# Parking_Lot_System_Main_Board.net
KiCad netlist of a schematic drawn in EAGLE
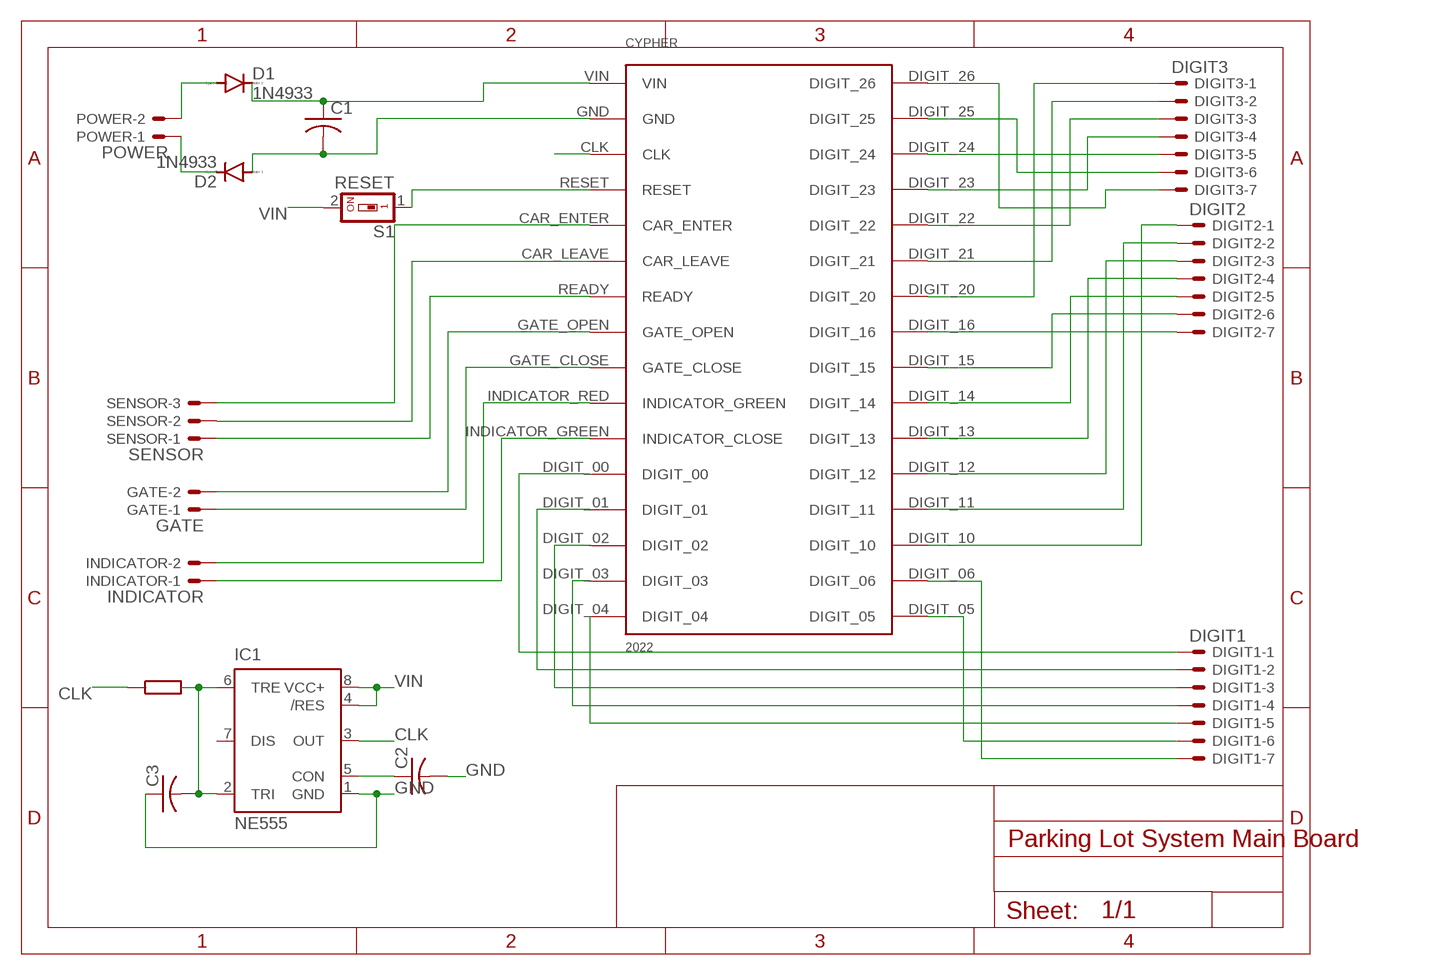
[diagram p0: schematic, sheet 1]

(export (version "E")
  (design (tool "Eeschema 10.0.6"))
  (components
    (comp (ref "C1")
      (value "C-US050-030X075")
      (footprint "eagle-import:C050-030X075")
      (libsource (lib "eagle-import") (part "C-US050-030X075"))
    )
    (comp (ref "C2")
      (value "C-US050-030X075")
      (footprint "eagle-import:C050-030X075")
      (libsource (lib "eagle-import") (part "C-US050-030X075"))
    )
    (comp (ref "C3")
      (value "C-US050-030X075")
      (footprint "eagle-import:C050-030X075")
      (libsource (lib "eagle-import") (part "C-US050-030X075"))
    )
    (comp (ref "CYPHER")
      (value "CYPHER2022")
      (footprint "eagle-import:CYPHER")
      (libsource (lib "eagle-import") (part "CYPHER2022"))
    )
    (comp (ref "D1")
      (value "1N4933")
      (footprint "eagle-import:DO41-10")
      (libsource (lib "eagle-import") (part "1N4933"))
    )
    (comp (ref "D2")
      (value "1N4933")
      (footprint "eagle-import:DO41-10")
      (libsource (lib "eagle-import") (part "1N4933"))
    )
    (comp (ref "DIGIT1")
      (value "DIGIT1")
      (footprint "eagle-import:22-23-2071")
      (fields (field (name "MF") "MOLEX") (field (name "MPN") "22-23-2071"))
      (libsource (lib "eagle-import") (part "22-23-2071"))
    )
    (comp (ref "DIGIT2")
      (value "DIGIT2")
      (footprint "eagle-import:22-23-2071")
      (fields (field (name "MF") "MOLEX") (field (name "MPN") "22-23-2071"))
      (libsource (lib "eagle-import") (part "22-23-2071"))
    )
    (comp (ref "DIGIT3")
      (value "DIGIT3")
      (footprint "eagle-import:22-23-2071")
      (fields (field (name "MF") "MOLEX") (field (name "MPN") "22-23-2071"))
      (libsource (lib "eagle-import") (part "22-23-2071"))
    )
    (comp (ref "GATE")
      (value "GATE")
      (footprint "eagle-import:22-23-2021")
      (fields (field (name "MF") "MOLEX") (field (name "MPN") "22-23-2021"))
      (libsource (lib "eagle-import") (part "22-23-2021"))
    )
    (comp (ref "IC1")
      (value "NE555")
      (footprint "eagle-import:DIL-08")
      (fields (field (name "MF") "Arrow Electronics") (field (name "MPN") "NE555N"))
      (libsource (lib "eagle-import") (part "NE555"))
    )
    (comp (ref "INDICATOR")
      (value "INDICATOR")
      (footprint "eagle-import:22-23-2021")
      (fields (field (name "MF") "MOLEX") (field (name "MPN") "22-23-2021"))
      (libsource (lib "eagle-import") (part "22-23-2021"))
    )
    (comp (ref "POWER")
      (value "POWER")
      (footprint "eagle-import:22-23-2021")
      (fields (field (name "MF") "MOLEX") (field (name "MPN") "22-23-2021"))
      (libsource (lib "eagle-import") (part "22-23-2021"))
    )
    (comp (ref "S1")
      (value "RESET")
      (footprint "eagle-import:SMS-001")
      (libsource (lib "eagle-import") (part "SWS001"))
    )
    (comp (ref "SENSOR")
      (value "SENSOR")
      (footprint "eagle-import:22-23-2031")
      (fields (field (name "MF") "MOLEX") (field (name "MPN") "22-23-2031"))
      (libsource (lib "eagle-import") (part "22-23-2031"))
    )
  )
  (nets
    (net (code "1") (name "/CLK") (class "Default")
      (node (ref "CYPHER") (pin "CLK") (pinfunction "CLK_CLK") (pintype "bidirectional"))
      (node (ref "IC1") (pin "3") (pinfunction "OUT_3") (pintype "output"))
    )
    (net (code "2") (name "/GND") (class "Default")
      (node (ref "C1") (pin "2") (pinfunction "2_2") (pintype "passive"))
      (node (ref "C2") (pin "2") (pinfunction "2_2") (pintype "passive"))
      (node (ref "C3") (pin "1") (pinfunction "1_1") (pintype "passive"))
      (node (ref "CYPHER") (pin "GND") (pinfunction "GND_GND") (pintype "bidirectional"))
      (node (ref "D2") (pin "A") (pinfunction "A_A") (pintype "passive"))
      (node (ref "IC1") (pin "1") (pinfunction "GND_1") (pintype "power_in"))
    )
    (net (code "3") (name "/VIN") (class "Default")
      (node (ref "C1") (pin "1") (pinfunction "1_1") (pintype "passive"))
      (node (ref "CYPHER") (pin "VIN") (pinfunction "VIN_VIN") (pintype "bidirectional"))
      (node (ref "D1") (pin "C") (pinfunction "C_C") (pintype "passive"))
      (node (ref "IC1") (pin "4") (pinfunction "/RES_4") (pintype "input"))
      (node (ref "IC1") (pin "8") (pinfunction "VCC+_8") (pintype "power_in"))
      (node (ref "S1") (pin "2") (pinfunction "2_2") (pintype "passive"))
    )
    (net (code "4") (name "Net-(CYPHER-INDICATOR_CLOSE)") (class "Default")
      (node (ref "CYPHER") (pin "INDICATOR_GREEN") (pinfunction "INDICATOR_CLOSE_INDICATOR_GREEN") (pintype "bidirectional"))
      (node (ref "INDICATOR") (pin "1") (pinfunction "S_1") (pintype "passive"))
    )
    (net (code "5") (name "Net-(CYPHER-INDICATOR_GREEN)") (class "Default")
      (node (ref "CYPHER") (pin "INDICATOR_RED") (pinfunction "INDICATOR_GREEN_INDICATOR_RED") (pintype "bidirectional"))
      (node (ref "INDICATOR") (pin "2") (pinfunction "S_2") (pintype "passive"))
    )
    (net (code "6") (name "Net-(CYPHER-PadRESET)") (class "Default")
      (node (ref "CYPHER") (pin "RESET") (pinfunction "RESET_RESET") (pintype "bidirectional"))
      (node (ref "S1") (pin "1") (pinfunction "1_1") (pintype "passive"))
    )
    (net (code "7") (name "Net-(DIGIT1A-S)") (class "Default")
      (node (ref "CYPHER") (pin "DIGIT_00") (pinfunction "DIGIT_00_DIGIT_00") (pintype "bidirectional"))
      (node (ref "DIGIT1") (pin "1") (pinfunction "S_1") (pintype "passive"))
    )
    (net (code "8") (name "Net-(DIGIT1B-S)") (class "Default")
      (node (ref "CYPHER") (pin "DIGIT_01") (pinfunction "DIGIT_01_DIGIT_01") (pintype "bidirectional"))
      (node (ref "DIGIT1") (pin "2") (pinfunction "S_2") (pintype "passive"))
    )
    (net (code "9") (name "Net-(DIGIT1C-S)") (class "Default")
      (node (ref "CYPHER") (pin "DIGIT_02") (pinfunction "DIGIT_02_DIGIT_02") (pintype "bidirectional"))
      (node (ref "DIGIT1") (pin "3") (pinfunction "S_3") (pintype "passive"))
    )
    (net (code "10") (name "Net-(DIGIT1D-S)") (class "Default")
      (node (ref "CYPHER") (pin "DIGIT_03") (pinfunction "DIGIT_03_DIGIT_03") (pintype "bidirectional"))
      (node (ref "DIGIT1") (pin "4") (pinfunction "S_4") (pintype "passive"))
    )
    (net (code "11") (name "Net-(DIGIT1E-S)") (class "Default")
      (node (ref "CYPHER") (pin "DIGIT_04") (pinfunction "DIGIT_04_DIGIT_04") (pintype "bidirectional"))
      (node (ref "DIGIT1") (pin "5") (pinfunction "S_5") (pintype "passive"))
    )
    (net (code "12") (name "Net-(DIGIT1F-S)") (class "Default")
      (node (ref "CYPHER") (pin "DIGIT_05") (pinfunction "DIGIT_05_DIGIT_05") (pintype "bidirectional"))
      (node (ref "DIGIT1") (pin "6") (pinfunction "S_6") (pintype "passive"))
    )
    (net (code "13") (name "Net-(DIGIT1G-S)") (class "Default")
      (node (ref "CYPHER") (pin "DIGIT_06") (pinfunction "DIGIT_06_DIGIT_06") (pintype "bidirectional"))
      (node (ref "DIGIT1") (pin "7") (pinfunction "S_7") (pintype "passive"))
    )
    (net (code "14") (name "Net-(DIGIT2A-S)") (class "Default")
      (node (ref "CYPHER") (pin "DIGIT_10") (pinfunction "DIGIT_10_DIGIT_10") (pintype "bidirectional"))
      (node (ref "DIGIT2") (pin "1") (pinfunction "S_1") (pintype "passive"))
    )
    (net (code "15") (name "Net-(DIGIT2B-S)") (class "Default")
      (node (ref "CYPHER") (pin "DIGIT_11") (pinfunction "DIGIT_11_DIGIT_11") (pintype "bidirectional"))
      (node (ref "DIGIT2") (pin "2") (pinfunction "S_2") (pintype "passive"))
    )
    (net (code "16") (name "Net-(DIGIT2C-S)") (class "Default")
      (node (ref "CYPHER") (pin "DIGIT_12") (pinfunction "DIGIT_12_DIGIT_12") (pintype "bidirectional"))
      (node (ref "DIGIT2") (pin "3") (pinfunction "S_3") (pintype "passive"))
    )
    (net (code "17") (name "Net-(DIGIT2D-S)") (class "Default")
      (node (ref "CYPHER") (pin "DIGIT_13") (pinfunction "DIGIT_13_DIGIT_13") (pintype "bidirectional"))
      (node (ref "DIGIT2") (pin "4") (pinfunction "S_4") (pintype "passive"))
    )
    (net (code "18") (name "Net-(DIGIT2E-S)") (class "Default")
      (node (ref "CYPHER") (pin "DIGIT_14") (pinfunction "DIGIT_14_DIGIT_14") (pintype "bidirectional"))
      (node (ref "DIGIT2") (pin "5") (pinfunction "S_5") (pintype "passive"))
    )
    (net (code "19") (name "Net-(DIGIT2F-S)") (class "Default")
      (node (ref "CYPHER") (pin "DIGIT_15") (pinfunction "DIGIT_15_DIGIT_15") (pintype "bidirectional"))
      (node (ref "DIGIT2") (pin "6") (pinfunction "S_6") (pintype "passive"))
    )
    (net (code "20") (name "Net-(DIGIT2G-S)") (class "Default")
      (node (ref "CYPHER") (pin "DIGIT_16") (pinfunction "DIGIT_16_DIGIT_16") (pintype "bidirectional"))
      (node (ref "DIGIT2") (pin "7") (pinfunction "S_7") (pintype "passive"))
    )
    (net (code "21") (name "Net-(DIGIT3A-S)") (class "Default")
      (node (ref "CYPHER") (pin "DIGIT_20") (pinfunction "DIGIT_20_DIGIT_20") (pintype "bidirectional"))
      (node (ref "DIGIT3") (pin "1") (pinfunction "S_1") (pintype "passive"))
    )
    (net (code "22") (name "Net-(DIGIT3B-S)") (class "Default")
      (node (ref "CYPHER") (pin "DIGIT_21") (pinfunction "DIGIT_21_DIGIT_21") (pintype "bidirectional"))
      (node (ref "DIGIT3") (pin "2") (pinfunction "S_2") (pintype "passive"))
    )
    (net (code "23") (name "Net-(DIGIT3C-S)") (class "Default")
      (node (ref "CYPHER") (pin "DIGIT_22") (pinfunction "DIGIT_22_DIGIT_22") (pintype "bidirectional"))
      (node (ref "DIGIT3") (pin "3") (pinfunction "S_3") (pintype "passive"))
    )
    (net (code "24") (name "Net-(DIGIT3D-S)") (class "Default")
      (node (ref "CYPHER") (pin "DIGIT_23") (pinfunction "DIGIT_23_DIGIT_23") (pintype "bidirectional"))
      (node (ref "DIGIT3") (pin "4") (pinfunction "S_4") (pintype "passive"))
    )
    (net (code "25") (name "Net-(DIGIT3E-S)") (class "Default")
      (node (ref "CYPHER") (pin "DIGIT_24") (pinfunction "DIGIT_24_DIGIT_24") (pintype "bidirectional"))
      (node (ref "DIGIT3") (pin "5") (pinfunction "S_5") (pintype "passive"))
    )
    (net (code "26") (name "Net-(DIGIT3F-S)") (class "Default")
      (node (ref "CYPHER") (pin "DIGIT_25") (pinfunction "DIGIT_25_DIGIT_25") (pintype "bidirectional"))
      (node (ref "DIGIT3") (pin "6") (pinfunction "S_6") (pintype "passive"))
    )
    (net (code "27") (name "Net-(DIGIT3G-S)") (class "Default")
      (node (ref "CYPHER") (pin "DIGIT_26") (pinfunction "DIGIT_26_DIGIT_26") (pintype "bidirectional"))
      (node (ref "DIGIT3") (pin "7") (pinfunction "S_7") (pintype "passive"))
    )
    (net (code "28") (name "Net-(GATEA-S)") (class "Default")
      (node (ref "CYPHER") (pin "GATE_CLOSE") (pinfunction "GATE_CLOSE_GATE_CLOSE") (pintype "bidirectional"))
      (node (ref "GATE") (pin "1") (pinfunction "S_1") (pintype "passive"))
    )
    (net (code "29") (name "Net-(GATEB-S)") (class "Default")
      (node (ref "CYPHER") (pin "GATE_OPEN") (pinfunction "GATE_OPEN_GATE_OPEN") (pintype "bidirectional"))
      (node (ref "GATE") (pin "2") (pinfunction "S_2") (pintype "passive"))
    )
    (net (code "30") (name "Net-(IC1-CON)") (class "Default")
      (node (ref "C2") (pin "1") (pinfunction "1_1") (pintype "passive"))
      (node (ref "IC1") (pin "5") (pinfunction "CON_5") (pintype "input"))
    )
    (net (code "31") (name "Net-(IC1-TRE)") (class "Default")
      (node (ref "C3") (pin "2") (pinfunction "2_2") (pintype "passive"))
      (node (ref "IC1") (pin "2") (pinfunction "TRI_2") (pintype "input"))
      (node (ref "IC1") (pin "6") (pinfunction "TRE_6") (pintype "input"))
    )
    (net (code "32") (name "Net-(POWERA-S)") (class "Default")
      (node (ref "D2") (pin "C") (pinfunction "C_C") (pintype "passive"))
      (node (ref "POWER") (pin "1") (pinfunction "S_1") (pintype "passive"))
    )
    (net (code "33") (name "Net-(POWERB-S)") (class "Default")
      (node (ref "D1") (pin "A") (pinfunction "A_A") (pintype "passive"))
      (node (ref "POWER") (pin "2") (pinfunction "S_2") (pintype "passive"))
    )
    (net (code "34") (name "Net-(SENSORA-S)") (class "Default")
      (node (ref "CYPHER") (pin "READY") (pinfunction "READY_READY") (pintype "bidirectional"))
      (node (ref "SENSOR") (pin "1") (pinfunction "S_1") (pintype "passive"))
    )
    (net (code "35") (name "Net-(SENSORB-S)") (class "Default")
      (node (ref "CYPHER") (pin "CAR_LEAVE") (pinfunction "CAR_LEAVE_CAR_LEAVE") (pintype "bidirectional"))
      (node (ref "SENSOR") (pin "2") (pinfunction "S_2") (pintype "passive"))
    )
    (net (code "36") (name "Net-(SENSORC-S)") (class "Default")
      (node (ref "CYPHER") (pin "CAR_ENTER") (pinfunction "CAR_ENTER_CAR_ENTER") (pintype "bidirectional"))
      (node (ref "SENSOR") (pin "3") (pinfunction "S_3") (pintype "passive"))
    )
    (net (code "37") (name "unconnected-(IC1-DIS-Pad7)") (class "Default")
      (node (ref "IC1") (pin "7") (pinfunction "DIS_7") (pintype "input"))
    )
  )
)
